# photoframe.net
KiCad netlist of a schematic drawn in EAGLE
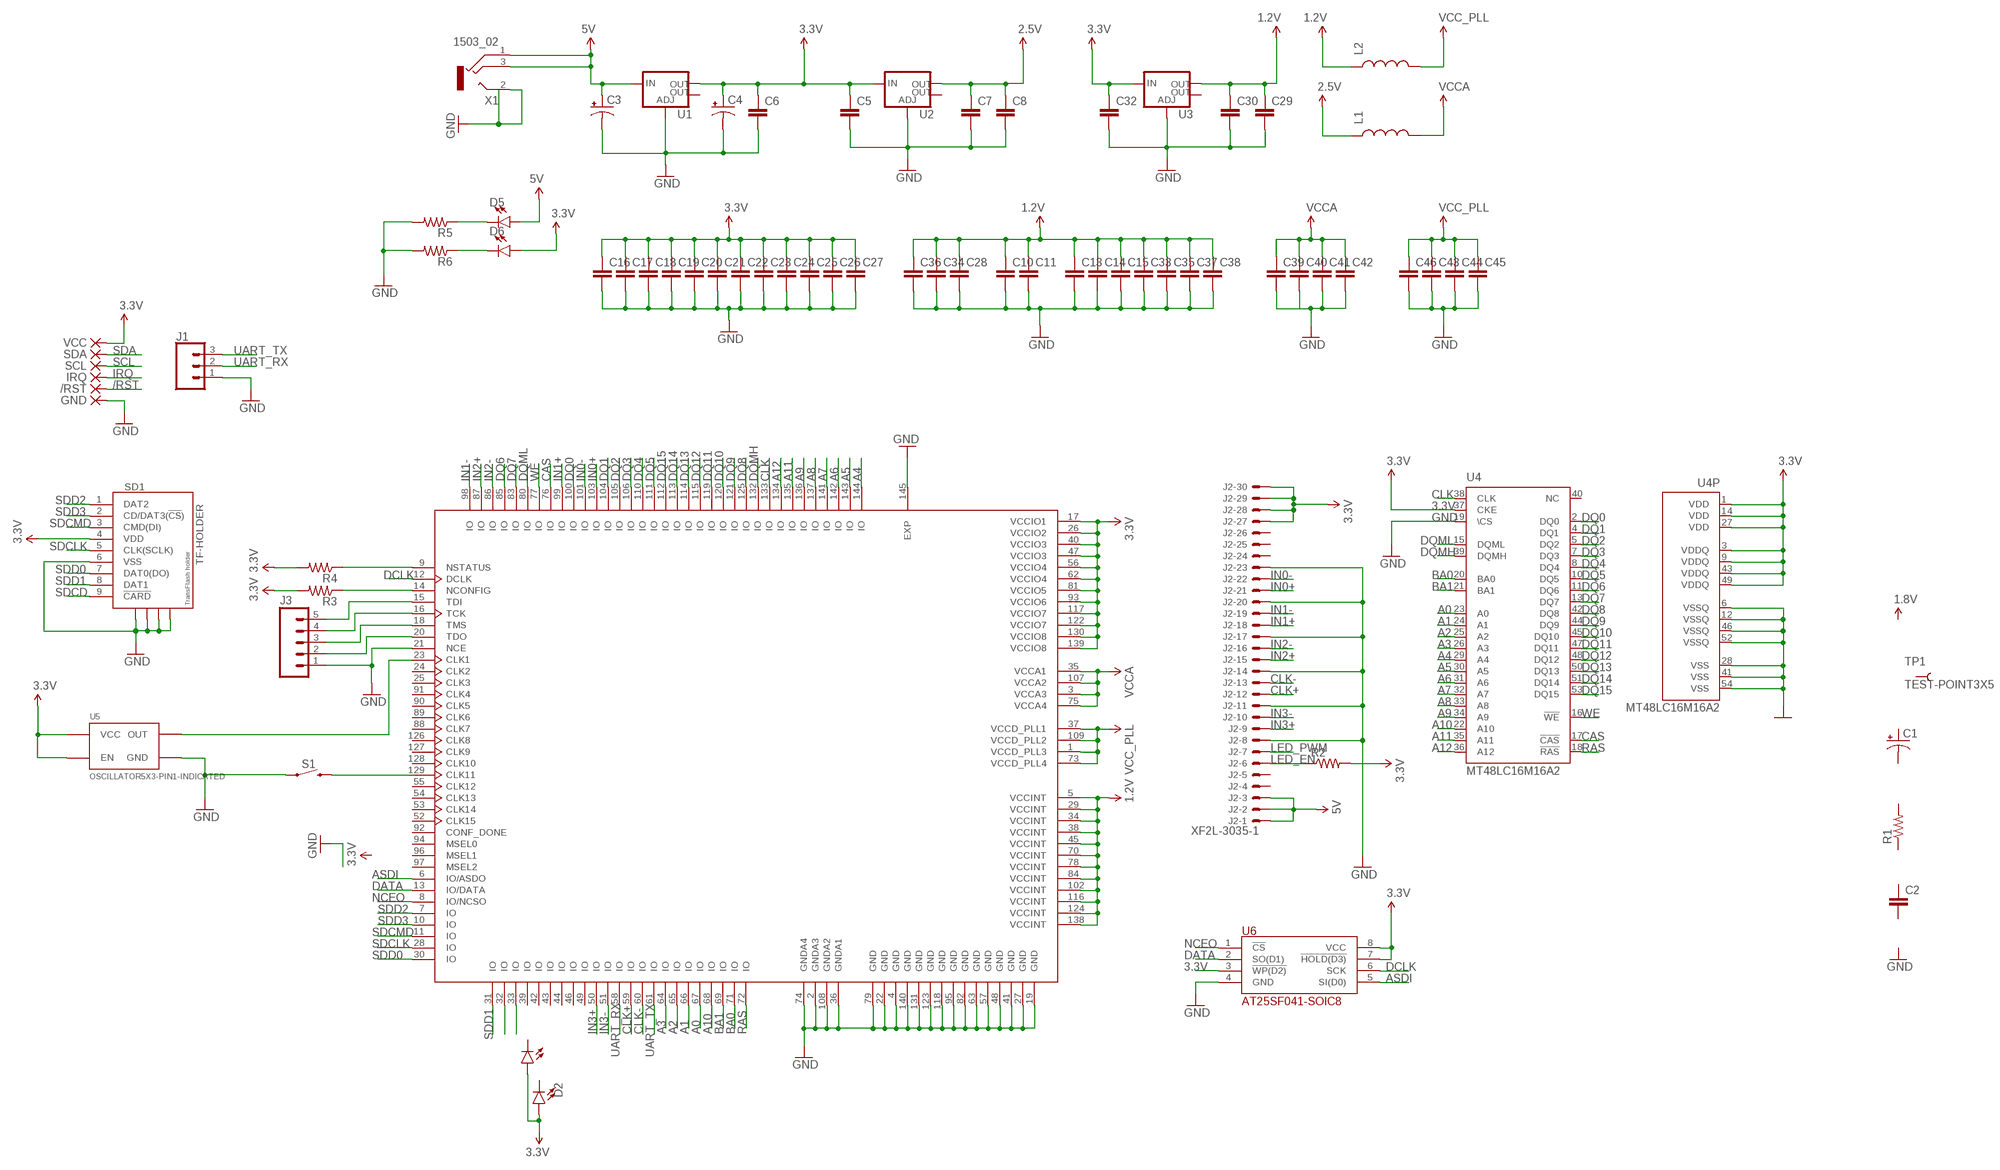
[diagram p0: schematic, sheet 1]

(export (version "E")
  (design (tool "Eeschema 10.0.6"))
  (components
    (comp (ref "/RST")
      (value "PAD-SMD15R")
      (footprint "eagle-import:SMD15R")
      (libsource (lib "eagle-import") (part "PAD-SMD15R"))
    )
    (comp (ref "C1")
      (value "CAP_POL1206-KIT")
      (footprint "eagle-import:EIA3216-KIT")
      (libsource (lib "eagle-import") (part "CAP_POL1206-KIT"))
    )
    (comp (ref "C2")
      (value "CAP0603-CAP")
      (footprint "eagle-import:0603-CAP")
      (libsource (lib "eagle-import") (part "CAP0603-CAP"))
    )
    (comp (ref "C3")
      (value "CAP_POL1206-KIT")
      (footprint "eagle-import:EIA3216-KIT")
      (libsource (lib "eagle-import") (part "CAP_POL1206-KIT"))
    )
    (comp (ref "C4")
      (value "CAP_POL1206-KIT")
      (footprint "eagle-import:EIA3216-KIT")
      (libsource (lib "eagle-import") (part "CAP_POL1206-KIT"))
    )
    (comp (ref "C5")
      (value "CAP1206")
      (footprint "eagle-import:1206")
      (libsource (lib "eagle-import") (part "CAP1206"))
    )
    (comp (ref "C6")
      (value "CAP0805")
      (footprint "eagle-import:0805")
      (libsource (lib "eagle-import") (part "CAP0805"))
    )
    (comp (ref "C7")
      (value "CAP1206")
      (footprint "eagle-import:1206")
      (libsource (lib "eagle-import") (part "CAP1206"))
    )
    (comp (ref "C8")
      (value "CAP0603-CAP")
      (footprint "eagle-import:0603-CAP")
      (libsource (lib "eagle-import") (part "CAP0603-CAP"))
    )
    (comp (ref "C10")
      (value "CAP0402-CAP")
      (footprint "eagle-import:0402-CAP")
      (libsource (lib "eagle-import") (part "CAP0402-CAP"))
    )
    (comp (ref "C11")
      (value "CAP0402-CAP")
      (footprint "eagle-import:0402-CAP")
      (libsource (lib "eagle-import") (part "CAP0402-CAP"))
    )
    (comp (ref "C13")
      (value "CAP0402-CAP")
      (footprint "eagle-import:0402-CAP")
      (libsource (lib "eagle-import") (part "CAP0402-CAP"))
    )
    (comp (ref "C14")
      (value "CAP0402-CAP")
      (footprint "eagle-import:0402-CAP")
      (libsource (lib "eagle-import") (part "CAP0402-CAP"))
    )
    (comp (ref "C15")
      (value "CAP0402-CAP")
      (footprint "eagle-import:0402-CAP")
      (libsource (lib "eagle-import") (part "CAP0402-CAP"))
    )
    (comp (ref "C16")
      (value "CAP0402-CAP")
      (footprint "eagle-import:0402-CAP")
      (libsource (lib "eagle-import") (part "CAP0402-CAP"))
    )
    (comp (ref "C17")
      (value "CAP0402-CAP")
      (footprint "eagle-import:0402-CAP")
      (libsource (lib "eagle-import") (part "CAP0402-CAP"))
    )
    (comp (ref "C18")
      (value "CAP0402-CAP")
      (footprint "eagle-import:0402-CAP")
      (libsource (lib "eagle-import") (part "CAP0402-CAP"))
    )
    (comp (ref "C19")
      (value "CAP0402-CAP")
      (footprint "eagle-import:0402-CAP")
      (libsource (lib "eagle-import") (part "CAP0402-CAP"))
    )
    (comp (ref "C20")
      (value "CAP0402-CAP")
      (footprint "eagle-import:0402-CAP")
      (libsource (lib "eagle-import") (part "CAP0402-CAP"))
    )
    (comp (ref "C21")
      (value "CAP0402-CAP")
      (footprint "eagle-import:0402-CAP")
      (libsource (lib "eagle-import") (part "CAP0402-CAP"))
    )
    (comp (ref "C22")
      (value "CAP0402-CAP")
      (footprint "eagle-import:0402-CAP")
      (libsource (lib "eagle-import") (part "CAP0402-CAP"))
    )
    (comp (ref "C23")
      (value "CAP0402-CAP")
      (footprint "eagle-import:0402-CAP")
      (libsource (lib "eagle-import") (part "CAP0402-CAP"))
    )
    (comp (ref "C24")
      (value "CAP0402-CAP")
      (footprint "eagle-import:0402-CAP")
      (libsource (lib "eagle-import") (part "CAP0402-CAP"))
    )
    (comp (ref "C25")
      (value "CAP0402-CAP")
      (footprint "eagle-import:0402-CAP")
      (libsource (lib "eagle-import") (part "CAP0402-CAP"))
    )
    (comp (ref "C26")
      (value "CAP0402-CAP")
      (footprint "eagle-import:0402-CAP")
      (libsource (lib "eagle-import") (part "CAP0402-CAP"))
    )
    (comp (ref "C27")
      (value "CAP0402-CAP")
      (footprint "eagle-import:0402-CAP")
      (libsource (lib "eagle-import") (part "CAP0402-CAP"))
    )
    (comp (ref "C28")
      (value "CAP0402-CAP")
      (footprint "eagle-import:0402-CAP")
      (libsource (lib "eagle-import") (part "CAP0402-CAP"))
    )
    (comp (ref "C29")
      (value "CAP0805")
      (footprint "eagle-import:0805")
      (libsource (lib "eagle-import") (part "CAP0805"))
    )
    (comp (ref "C30")
      (value "CAP1206")
      (footprint "eagle-import:1206")
      (libsource (lib "eagle-import") (part "CAP1206"))
    )
    (comp (ref "C32")
      (value "CAP1206")
      (footprint "eagle-import:1206")
      (libsource (lib "eagle-import") (part "CAP1206"))
    )
    (comp (ref "C33")
      (value "CAP0402-CAP")
      (footprint "eagle-import:0402-CAP")
      (libsource (lib "eagle-import") (part "CAP0402-CAP"))
    )
    (comp (ref "C34")
      (value "CAP0402-CAP")
      (footprint "eagle-import:0402-CAP")
      (libsource (lib "eagle-import") (part "CAP0402-CAP"))
    )
    (comp (ref "C35")
      (value "CAP0402-CAP")
      (footprint "eagle-import:0402-CAP")
      (libsource (lib "eagle-import") (part "CAP0402-CAP"))
    )
    (comp (ref "C36")
      (value "CAP0402-CAP")
      (footprint "eagle-import:0402-CAP")
      (libsource (lib "eagle-import") (part "CAP0402-CAP"))
    )
    (comp (ref "C37")
      (value "CAP0402-CAP")
      (footprint "eagle-import:0402-CAP")
      (libsource (lib "eagle-import") (part "CAP0402-CAP"))
    )
    (comp (ref "C38")
      (value "CAP0402-CAP")
      (footprint "eagle-import:0402-CAP")
      (libsource (lib "eagle-import") (part "CAP0402-CAP"))
    )
    (comp (ref "C39")
      (value "CAP0402-CAP")
      (footprint "eagle-import:0402-CAP")
      (libsource (lib "eagle-import") (part "CAP0402-CAP"))
    )
    (comp (ref "C40")
      (value "CAP0402-CAP")
      (footprint "eagle-import:0402-CAP")
      (libsource (lib "eagle-import") (part "CAP0402-CAP"))
    )
    (comp (ref "C41")
      (value "CAP0402-CAP")
      (footprint "eagle-import:0402-CAP")
      (libsource (lib "eagle-import") (part "CAP0402-CAP"))
    )
    (comp (ref "C42")
      (value "CAP0402-CAP")
      (footprint "eagle-import:0402-CAP")
      (libsource (lib "eagle-import") (part "CAP0402-CAP"))
    )
    (comp (ref "C43")
      (value "CAP0402-CAP")
      (footprint "eagle-import:0402-CAP")
      (libsource (lib "eagle-import") (part "CAP0402-CAP"))
    )
    (comp (ref "C44")
      (value "CAP0402-CAP")
      (footprint "eagle-import:0402-CAP")
      (libsource (lib "eagle-import") (part "CAP0402-CAP"))
    )
    (comp (ref "C45")
      (value "CAP0805")
      (footprint "eagle-import:0805")
      (libsource (lib "eagle-import") (part "CAP0805"))
    )
    (comp (ref "C46")
      (value "CAP0402-CAP")
      (footprint "eagle-import:0402-CAP")
      (libsource (lib "eagle-import") (part "CAP0402-CAP"))
    )
    (comp (ref "D1")
      (value "LED0603")
      (footprint "eagle-import:LED-0603")
      (libsource (lib "eagle-import") (part "LED0603"))
    )
    (comp (ref "D2")
      (value "LED0603")
      (footprint "eagle-import:LED-0603")
      (libsource (lib "eagle-import") (part "LED0603"))
    )
    (comp (ref "D5")
      (value "LED1206")
      (footprint "eagle-import:LED-1206")
      (libsource (lib "eagle-import") (part "LED1206"))
    )
    (comp (ref "D6")
      (value "LED1206")
      (footprint "eagle-import:LED-1206")
      (libsource (lib "eagle-import") (part "LED1206"))
    )
    (comp (ref "GND")
      (value "PAD-SMD14R")
      (footprint "eagle-import:SMD14R")
      (libsource (lib "eagle-import") (part "PAD-SMD14R"))
    )
    (comp (ref "IRQ")
      (value "PAD-SMD15R")
      (footprint "eagle-import:SMD15R")
      (libsource (lib "eagle-import") (part "PAD-SMD15R"))
    )
    (comp (ref "J1")
      (value "CONN_03LONGPADS")
      (footprint "eagle-import:1X03_LONGPADS")
      (libsource (lib "eagle-import") (part "CONN_03LONGPADS"))
    )
    (comp (ref "J2")
      (value "XF2L-3035-1")
      (footprint "eagle-import:XF2L-3035-1")
      (fields (field (name "MPN") "XF2L-3035-1A"))
      (libsource (lib "eagle-import") (part "XF2-30?35-1L"))
    )
    (comp (ref "J3")
      (value "M05PTH_LONGPADS")
      (footprint "eagle-import:1X05_LONGPADS")
      (libsource (lib "eagle-import") (part "M05PTH_LONGPADS"))
    )
    (comp (ref "L1")
      (value "INDUCTOR0805-IND")
      (footprint "eagle-import:0805")
      (libsource (lib "eagle-import") (part "INDUCTOR0805-IND"))
    )
    (comp (ref "L2")
      (value "INDUCTOR0805-IND")
      (footprint "eagle-import:0805")
      (libsource (lib "eagle-import") (part "INDUCTOR0805-IND"))
    )
    (comp (ref "R1")
      (value "RESISTOR0603-RES")
      (footprint "eagle-import:0603-RES")
      (libsource (lib "eagle-import") (part "RESISTOR0603-RES"))
    )
    (comp (ref "R2")
      (value "RESISTOR0402-RES")
      (footprint "eagle-import:0402-RES")
      (libsource (lib "eagle-import") (part "RESISTOR0402-RES"))
    )
    (comp (ref "R3")
      (value "RESISTOR0402-RES")
      (footprint "eagle-import:0402-RES")
      (libsource (lib "eagle-import") (part "RESISTOR0402-RES"))
    )
    (comp (ref "R4")
      (value "RESISTOR0402-RES")
      (footprint "eagle-import:0402-RES")
      (libsource (lib "eagle-import") (part "RESISTOR0402-RES"))
    )
    (comp (ref "R5")
      (value "RESISTOR0603-RES")
      (footprint "eagle-import:0603-RES")
      (libsource (lib "eagle-import") (part "RESISTOR0603-RES"))
    )
    (comp (ref "R6")
      (value "RESISTOR0603-RES")
      (footprint "eagle-import:0603-RES")
      (libsource (lib "eagle-import") (part "RESISTOR0603-RES"))
    )
    (comp (ref "S1")
      (value "MOMENTARY-SWITCH-SPST-SMD-5.2-TALL-REDUNDANT")
      (footprint "eagle-import:TACTILE_SWITCH_SMD_5.2MM")
      (libsource (lib "eagle-import") (part "MOMENTARY-SWITCH-SPST-SMD-5.2-TALL-REDUNDANT"))
    )
    (comp (ref "SCL")
      (value "PAD-SMD15R")
      (footprint "eagle-import:SMD15R")
      (libsource (lib "eagle-import") (part "PAD-SMD15R"))
    )
    (comp (ref "SD1")
      (value "TF-HOLDER")
      (footprint "eagle-import:TF-PULL")
      (libsource (lib "eagle-import") (part "TF-HOLDER"))
    )
    (comp (ref "SDA")
      (value "PAD-SMD15R")
      (footprint "eagle-import:SMD15R")
      (libsource (lib "eagle-import") (part "PAD-SMD15R"))
    )
    (comp (ref "TP1")
      (value "TEST-POINT3X5")
      (footprint "eagle-import:PAD.03X.05")
      (libsource (lib "eagle-import") (part "TEST-POINT3X5"))
    )
    (comp (ref "U0")
      (value "EP4CE15E22")
      (footprint "eagle-import:QFP50P2200X2200X165-145N")
      (libsource (lib "eagle-import") (part "EP4CE15E22"))
    )
    (comp (ref "U1")
      (value "V_REG_LM1117SOT223")
      (footprint "eagle-import:SOT223")
      (libsource (lib "eagle-import") (part "V_REG_LM1117SOT223"))
    )
    (comp (ref "U2")
      (value "V_REG_LM1117SOT223")
      (footprint "eagle-import:SOT223")
      (libsource (lib "eagle-import") (part "V_REG_LM1117SOT223"))
    )
    (comp (ref "U3")
      (value "V_REG_LM1117SOT223")
      (footprint "eagle-import:SOT223")
      (libsource (lib "eagle-import") (part "V_REG_LM1117SOT223"))
    )
    (comp (ref "U4")
      (value "MT48LC16M16A2")
      (footprint "eagle-import:TSOP54-400")
      (libsource (lib "eagle-import") (part "MT48LC16M16A2"))
    )
    (comp (ref "U5")
      (value "OSCILLATOR5X3-PIN1-INDICATED")
      (footprint "eagle-import:CRYSTAL-OSC-SMD-5X3")
      (libsource (lib "eagle-import") (part "OSCILLATOR5X3-PIN1-INDICATED"))
    )
    (comp (ref "U6")
      (value "AT25SF041-SOIC8")
      (footprint "eagle-import:SO08")
      (libsource (lib "eagle-import") (part "AT25SF041"))
    )
    (comp (ref "VCC")
      (value "PAD-SMD15R")
      (footprint "eagle-import:SMD15R")
      (libsource (lib "eagle-import") (part "PAD-SMD15R"))
    )
    (comp (ref "X1")
      (value "1503_02")
      (footprint "eagle-import:1503_02")
      (libsource (lib "eagle-import") (part "1503_02"))
    )
  )
  (nets
    (net (code "1") (name "/A0") (class "Default")
      (node (ref "U0") (pin "67") (pinfunction "IO_67") (pintype "bidirectional"))
      (node (ref "U4") (pin "23") (pinfunction "A0_23") (pintype "input"))
    )
    (net (code "2") (name "/A1") (class "Default")
      (node (ref "U0") (pin "66") (pinfunction "IO_66") (pintype "bidirectional"))
      (node (ref "U4") (pin "24") (pinfunction "A1_24") (pintype "input"))
    )
    (net (code "3") (name "/A2") (class "Default")
      (node (ref "U0") (pin "65") (pinfunction "IO_65") (pintype "bidirectional"))
      (node (ref "U4") (pin "25") (pinfunction "A2_25") (pintype "input"))
    )
    (net (code "4") (name "/A3") (class "Default")
      (node (ref "U0") (pin "64") (pinfunction "IO_64") (pintype "bidirectional"))
      (node (ref "U4") (pin "26") (pinfunction "A3_26") (pintype "input"))
    )
    (net (code "5") (name "/A4") (class "Default")
      (node (ref "U0") (pin "144") (pinfunction "IO_144") (pintype "bidirectional"))
      (node (ref "U4") (pin "29") (pinfunction "A4_29") (pintype "input"))
    )
    (net (code "6") (name "/A5") (class "Default")
      (node (ref "U0") (pin "143") (pinfunction "IO_143") (pintype "bidirectional"))
      (node (ref "U4") (pin "30") (pinfunction "A5_30") (pintype "input"))
    )
    (net (code "7") (name "/A6") (class "Default")
      (node (ref "U0") (pin "142") (pinfunction "IO_142") (pintype "bidirectional"))
      (node (ref "U4") (pin "31") (pinfunction "A6_31") (pintype "input"))
    )
    (net (code "8") (name "/A7") (class "Default")
      (node (ref "U0") (pin "141") (pinfunction "IO_141") (pintype "bidirectional"))
      (node (ref "U4") (pin "32") (pinfunction "A7_32") (pintype "input"))
    )
    (net (code "9") (name "/A8") (class "Default")
      (node (ref "U0") (pin "137") (pinfunction "IO_137") (pintype "bidirectional"))
      (node (ref "U4") (pin "33") (pinfunction "A8_33") (pintype "input"))
    )
    (net (code "10") (name "/A9") (class "Default")
      (node (ref "U0") (pin "136") (pinfunction "IO_136") (pintype "bidirectional"))
      (node (ref "U4") (pin "34") (pinfunction "A9_34") (pintype "input"))
    )
    (net (code "11") (name "/A10") (class "Default")
      (node (ref "U0") (pin "68") (pinfunction "IO_68") (pintype "bidirectional"))
      (node (ref "U4") (pin "22") (pinfunction "A10_22") (pintype "input"))
    )
    (net (code "12") (name "/A11") (class "Default")
      (node (ref "U0") (pin "135") (pinfunction "IO_135") (pintype "bidirectional"))
      (node (ref "U4") (pin "35") (pinfunction "A11_35") (pintype "input"))
    )
    (net (code "13") (name "/A12") (class "Default")
      (node (ref "U0") (pin "134") (pinfunction "IO_134") (pintype "bidirectional"))
      (node (ref "U4") (pin "36") (pinfunction "A12_36") (pintype "input"))
    )
    (net (code "14") (name "/ASDI") (class "Default")
      (node (ref "U0") (pin "6") (pinfunction "IO/ASDO_6") (pintype "bidirectional"))
      (node (ref "U6") (pin "5") (pinfunction "SI(D0)_5") (pintype "bidirectional"))
    )
    (net (code "15") (name "/BA0") (class "Default")
      (node (ref "U0") (pin "71") (pinfunction "IO_71") (pintype "bidirectional"))
      (node (ref "U4") (pin "20") (pinfunction "BA0_20") (pintype "input"))
    )
    (net (code "16") (name "/BA1") (class "Default")
      (node (ref "U0") (pin "69") (pinfunction "IO_69") (pintype "bidirectional"))
      (node (ref "U4") (pin "21") (pinfunction "BA1_21") (pintype "input"))
    )
    (net (code "17") (name "/CAS") (class "Default")
      (node (ref "U0") (pin "76") (pinfunction "IO_76") (pintype "bidirectional"))
      (node (ref "U4") (pin "17") (pinfunction "~{CAS}_17") (pintype "input"))
    )
    (net (code "18") (name "/CLK") (class "Default")
      (node (ref "U0") (pin "133") (pinfunction "IO_133") (pintype "bidirectional"))
      (node (ref "U4") (pin "38") (pinfunction "CLK_38") (pintype "input"))
    )
    (net (code "19") (name "/CLK+") (class "Default")
      (node (ref "J2") (pin "12") (pinfunction "MS_12") (pintype "passive"))
      (node (ref "U0") (pin "59") (pinfunction "IO_59") (pintype "bidirectional"))
    )
    (net (code "20") (name "/CLK-") (class "Default")
      (node (ref "J2") (pin "13") (pinfunction "MS_13") (pintype "passive"))
      (node (ref "U0") (pin "60") (pinfunction "IO_60") (pintype "bidirectional"))
    )
    (net (code "21") (name "/DATA") (class "Default")
      (node (ref "U0") (pin "13") (pinfunction "IO/DATA_13") (pintype "bidirectional"))
      (node (ref "U6") (pin "2") (pinfunction "SO(D1)_2") (pintype "bidirectional"))
    )
    (net (code "22") (name "/DCLK") (class "Default")
      (node (ref "U0") (pin "12") (pinfunction "DCLK_12") (pintype "bidirectional"))
      (node (ref "U6") (pin "6") (pinfunction "SCK_6") (pintype "bidirectional"))
    )
    (net (code "23") (name "/DQ0") (class "Default")
      (node (ref "U0") (pin "100") (pinfunction "IO_100") (pintype "bidirectional"))
      (node (ref "U4") (pin "2") (pinfunction "DQ0_2") (pintype "tri_state"))
    )
    (net (code "24") (name "/DQ1") (class "Default")
      (node (ref "U0") (pin "104") (pinfunction "IO_104") (pintype "bidirectional"))
      (node (ref "U4") (pin "4") (pinfunction "DQ1_4") (pintype "tri_state"))
    )
    (net (code "25") (name "/DQ2") (class "Default")
      (node (ref "U0") (pin "105") (pinfunction "IO_105") (pintype "bidirectional"))
      (node (ref "U4") (pin "5") (pinfunction "DQ2_5") (pintype "tri_state"))
    )
    (net (code "26") (name "/DQ3") (class "Default")
      (node (ref "U0") (pin "106") (pinfunction "IO_106") (pintype "bidirectional"))
      (node (ref "U4") (pin "7") (pinfunction "DQ3_7") (pintype "tri_state"))
    )
    (net (code "27") (name "/DQ4") (class "Default")
      (node (ref "U0") (pin "110") (pinfunction "IO_110") (pintype "bidirectional"))
      (node (ref "U4") (pin "8") (pinfunction "DQ4_8") (pintype "tri_state"))
    )
    (net (code "28") (name "/DQ5") (class "Default")
      (node (ref "U0") (pin "111") (pinfunction "IO_111") (pintype "bidirectional"))
      (node (ref "U4") (pin "10") (pinfunction "DQ5_10") (pintype "tri_state"))
    )
    (net (code "29") (name "/DQ6") (class "Default")
      (node (ref "U0") (pin "85") (pinfunction "IO_85") (pintype "bidirectional"))
      (node (ref "U4") (pin "11") (pinfunction "DQ6_11") (pintype "tri_state"))
    )
    (net (code "30") (name "/DQ7") (class "Default")
      (node (ref "U0") (pin "83") (pinfunction "IO_83") (pintype "bidirectional"))
      (node (ref "U4") (pin "13") (pinfunction "DQ7_13") (pintype "tri_state"))
    )
    (net (code "31") (name "/DQ8") (class "Default")
      (node (ref "U0") (pin "125") (pinfunction "IO_125") (pintype "bidirectional"))
      (node (ref "U4") (pin "42") (pinfunction "DQ8_42") (pintype "tri_state"))
    )
    (net (code "32") (name "/DQ9") (class "Default")
      (node (ref "U0") (pin "121") (pinfunction "IO_121") (pintype "bidirectional"))
      (node (ref "U4") (pin "44") (pinfunction "DQ9_44") (pintype "tri_state"))
    )
    (net (code "33") (name "/DQ10") (class "Default")
      (node (ref "U0") (pin "120") (pinfunction "IO_120") (pintype "bidirectional"))
      (node (ref "U4") (pin "45") (pinfunction "DQ10_45") (pintype "tri_state"))
    )
    (net (code "34") (name "/DQ11") (class "Default")
      (node (ref "U0") (pin "119") (pinfunction "IO_119") (pintype "bidirectional"))
      (node (ref "U4") (pin "47") (pinfunction "DQ11_47") (pintype "tri_state"))
    )
    (net (code "35") (name "/DQ12") (class "Default")
      (node (ref "U0") (pin "115") (pinfunction "IO_115") (pintype "bidirectional"))
      (node (ref "U4") (pin "48") (pinfunction "DQ12_48") (pintype "tri_state"))
    )
    (net (code "36") (name "/DQ13") (class "Default")
      (node (ref "U0") (pin "114") (pinfunction "IO_114") (pintype "bidirectional"))
      (node (ref "U4") (pin "50") (pinfunction "DQ13_50") (pintype "tri_state"))
    )
    (net (code "37") (name "/DQ14") (class "Default")
      (node (ref "U0") (pin "113") (pinfunction "IO_113") (pintype "bidirectional"))
      (node (ref "U4") (pin "51") (pinfunction "DQ14_51") (pintype "tri_state"))
    )
    (net (code "38") (name "/DQ15") (class "Default")
      (node (ref "U0") (pin "112") (pinfunction "IO_112") (pintype "bidirectional"))
      (node (ref "U4") (pin "53") (pinfunction "DQ15_53") (pintype "tri_state"))
    )
    (net (code "39") (name "/DQMH") (class "Default")
      (node (ref "U0") (pin "132") (pinfunction "IO_132") (pintype "bidirectional"))
      (node (ref "U4") (pin "39") (pinfunction "DQMH_39") (pintype "input"))
    )
    (net (code "40") (name "/DQML") (class "Default")
      (node (ref "U0") (pin "80") (pinfunction "IO_80") (pintype "bidirectional"))
      (node (ref "U4") (pin "15") (pinfunction "DQML_15") (pintype "input"))
    )
    (net (code "41") (name "/IN0+") (class "Default")
      (node (ref "J2") (pin "21") (pinfunction "MS_21") (pintype "passive"))
      (node (ref "U0") (pin "103") (pinfunction "IO_103") (pintype "bidirectional"))
    )
    (net (code "42") (name "/IN0-") (class "Default")
      (node (ref "J2") (pin "22") (pinfunction "MS_22") (pintype "passive"))
      (node (ref "U0") (pin "101") (pinfunction "IO_101") (pintype "bidirectional"))
    )
    (net (code "43") (name "/IN1+") (class "Default")
      (node (ref "J2") (pin "18") (pinfunction "MS_18") (pintype "passive"))
      (node (ref "U0") (pin "99") (pinfunction "IO_99") (pintype "bidirectional"))
    )
    (net (code "44") (name "/IN1-") (class "Default")
      (node (ref "J2") (pin "19") (pinfunction "MS_19") (pintype "passive"))
      (node (ref "U0") (pin "98") (pinfunction "IO_98") (pintype "bidirectional"))
    )
    (net (code "45") (name "/IN2+") (class "Default")
      (node (ref "J2") (pin "15") (pinfunction "MS_15") (pintype "passive"))
      (node (ref "U0") (pin "87") (pinfunction "IO_87") (pintype "bidirectional"))
    )
    (net (code "46") (name "/IN2-") (class "Default")
      (node (ref "J2") (pin "16") (pinfunction "MS_16") (pintype "passive"))
      (node (ref "U0") (pin "86") (pinfunction "IO_86") (pintype "bidirectional"))
    )
    (net (code "47") (name "/IN3+") (class "Default")
      (node (ref "J2") (pin "9") (pinfunction "MS_9") (pintype "passive"))
      (node (ref "U0") (pin "50") (pinfunction "IO_50") (pintype "bidirectional"))
    )
    (net (code "48") (name "/IN3-") (class "Default")
      (node (ref "J2") (pin "10") (pinfunction "MS_10") (pintype "passive"))
      (node (ref "U0") (pin "51") (pinfunction "IO_51") (pintype "bidirectional"))
    )
    (net (code "49") (name "/IRQ") (class "Default")
      (node (ref "IRQ") (pin "PAD") (pinfunction "P_PAD") (pintype "passive"))
    )
    (net (code "50") (name "/LED_EN") (class "Default")
      (node (ref "J2") (pin "6") (pinfunction "MS_6") (pintype "passive"))
      (node (ref "R2") (pin "1") (pinfunction "1_1") (pintype "passive"))
    )
    (net (code "51") (name "/LED_PWM") (class "Default")
      (node (ref "J2") (pin "7") (pinfunction "MS_7") (pintype "passive"))
    )
    (net (code "52") (name "/NCEO") (class "Default")
      (node (ref "U0") (pin "8") (pinfunction "IO/NCSO_8") (pintype "bidirectional"))
      (node (ref "U6") (pin "1") (pinfunction "~{CS}_1") (pintype "bidirectional"))
    )
    (net (code "53") (name "/RAS") (class "Default")
      (node (ref "U0") (pin "72") (pinfunction "IO_72") (pintype "bidirectional"))
      (node (ref "U4") (pin "18") (pinfunction "~{RAS}_18") (pintype "input"))
    )
    (net (code "54") (name "/SCL") (class "Default")
      (node (ref "SCL") (pin "PAD") (pinfunction "P_PAD") (pintype "passive"))
    )
    (net (code "55") (name "/SDA") (class "Default")
      (node (ref "SDA") (pin "PAD") (pinfunction "P_PAD") (pintype "passive"))
    )
    (net (code "56") (name "/SDCD") (class "Default")
      (node (ref "SD1") (pin "9") (pinfunction "~{CARD}_9") (pintype "passive"))
    )
    (net (code "57") (name "/SDCLK") (class "Default")
      (node (ref "SD1") (pin "5") (pinfunction "CLK(SCLK)_5") (pintype "input"))
      (node (ref "U0") (pin "28") (pinfunction "IO_28") (pintype "bidirectional"))
    )
    (net (code "58") (name "/SDCMD") (class "Default")
      (node (ref "SD1") (pin "3") (pinfunction "CMD(DI)_3") (pintype "bidirectional"))
      (node (ref "U0") (pin "11") (pinfunction "IO_11") (pintype "bidirectional"))
    )
    (net (code "59") (name "/SDD0") (class "Default")
      (node (ref "SD1") (pin "7") (pinfunction "DAT0(DO)_7") (pintype "bidirectional"))
      (node (ref "U0") (pin "30") (pinfunction "IO_30") (pintype "bidirectional"))
    )
    (net (code "60") (name "/SDD1") (class "Default")
      (node (ref "SD1") (pin "8") (pinfunction "DAT1_8") (pintype "bidirectional"))
      (node (ref "U0") (pin "31") (pinfunction "IO_31") (pintype "bidirectional"))
    )
    (net (code "61") (name "/SDD2") (class "Default")
      (node (ref "SD1") (pin "1") (pinfunction "DAT2_1") (pintype "bidirectional"))
      (node (ref "U0") (pin "7") (pinfunction "IO_7") (pintype "bidirectional"))
    )
    (net (code "62") (name "/SDD3") (class "Default")
      (node (ref "SD1") (pin "2") (pinfunction "CD/DAT3(~{CS})_2") (pintype "bidirectional"))
      (node (ref "U0") (pin "10") (pinfunction "IO_10") (pintype "bidirectional"))
    )
    (net (code "63") (name "/UART_RX") (class "Default")
      (node (ref "J1") (pin "2") (pinfunction "2_2") (pintype "passive"))
      (node (ref "U0") (pin "58") (pinfunction "IO_58") (pintype "bidirectional"))
    )
    (net (code "64") (name "/UART_TX") (class "Default")
      (node (ref "J1") (pin "3") (pinfunction "3_3") (pintype "passive"))
      (node (ref "U0") (pin "61") (pinfunction "IO_61") (pintype "bidirectional"))
    )
    (net (code "65") (name "/WE") (class "Default")
      (node (ref "U0") (pin "77") (pinfunction "IO_77") (pintype "bidirectional"))
      (node (ref "U4") (pin "16") (pinfunction "~{WE}_16") (pintype "input"))
    )
    (net (code "66") (name "/{slash}RST") (class "Default")
      (node (ref "/RST") (pin "PAD") (pinfunction "P_PAD") (pintype "passive"))
    )
    (net (code "67") (name "1.2V") (class "Default")
      (node (ref "C10") (pin "1") (pinfunction "1_1") (pintype "passive"))
      (node (ref "C11") (pin "1") (pinfunction "1_1") (pintype "passive"))
      (node (ref "C13") (pin "1") (pinfunction "1_1") (pintype "passive"))
      (node (ref "C14") (pin "1") (pinfunction "1_1") (pintype "passive"))
      (node (ref "C15") (pin "1") (pinfunction "1_1") (pintype "passive"))
      (node (ref "C28") (pin "1") (pinfunction "1_1") (pintype "passive"))
      (node (ref "C29") (pin "1") (pinfunction "1_1") (pintype "passive"))
      (node (ref "C30") (pin "1") (pinfunction "1_1") (pintype "passive"))
      (node (ref "C33") (pin "1") (pinfunction "1_1") (pintype "passive"))
      (node (ref "C34") (pin "1") (pinfunction "1_1") (pintype "passive"))
      (node (ref "C35") (pin "1") (pinfunction "1_1") (pintype "passive"))
      (node (ref "C36") (pin "1") (pinfunction "1_1") (pintype "passive"))
      (node (ref "C37") (pin "1") (pinfunction "1_1") (pintype "passive"))
      (node (ref "C38") (pin "1") (pinfunction "1_1") (pintype "passive"))
      (node (ref "L2") (pin "1") (pinfunction "1_1") (pintype "passive"))
      (node (ref "U0") (pin "102") (pinfunction "VCCINT_102") (pintype "power_in"))
      (node (ref "U0") (pin "116") (pinfunction "VCCINT_116") (pintype "power_in"))
      (node (ref "U0") (pin "124") (pinfunction "VCCINT_124") (pintype "power_in"))
      (node (ref "U0") (pin "138") (pinfunction "VCCINT_138") (pintype "power_in"))
      (node (ref "U0") (pin "29") (pinfunction "VCCINT_29") (pintype "power_in"))
      (node (ref "U0") (pin "34") (pinfunction "VCCINT_34") (pintype "power_in"))
      (node (ref "U0") (pin "38") (pinfunction "VCCINT_38") (pintype "power_in"))
      (node (ref "U0") (pin "45") (pinfunction "VCCINT_45") (pintype "power_in"))
      (node (ref "U0") (pin "5") (pinfunction "VCCINT_5") (pintype "power_in"))
      (node (ref "U0") (pin "70") (pinfunction "VCCINT_70") (pintype "power_in"))
      (node (ref "U0") (pin "78") (pinfunction "VCCINT_78") (pintype "power_in"))
      (node (ref "U0") (pin "84") (pinfunction "VCCINT_84") (pintype "power_in"))
      (node (ref "U3") (pin "2") (pinfunction "OUT_2") (pintype "output"))
    )
    (net (code "69") (name "2.5V") (class "Default")
      (node (ref "C7") (pin "1") (pinfunction "1_1") (pintype "passive"))
      (node (ref "C8") (pin "1") (pinfunction "1_1") (pintype "passive"))
      (node (ref "L1") (pin "1") (pinfunction "1_1") (pintype "passive"))
      (node (ref "U2") (pin "2") (pinfunction "OUT_2") (pintype "output"))
    )
    (net (code "70") (name "3.3V") (class "Default")
      (node (ref "C16") (pin "1") (pinfunction "1_1") (pintype "passive"))
      (node (ref "C17") (pin "1") (pinfunction "1_1") (pintype "passive"))
      (node (ref "C18") (pin "1") (pinfunction "1_1") (pintype "passive"))
      (node (ref "C19") (pin "1") (pinfunction "1_1") (pintype "passive"))
      (node (ref "C20") (pin "1") (pinfunction "1_1") (pintype "passive"))
      (node (ref "C21") (pin "1") (pinfunction "1_1") (pintype "passive"))
      (node (ref "C22") (pin "1") (pinfunction "1_1") (pintype "passive"))
      (node (ref "C23") (pin "1") (pinfunction "1_1") (pintype "passive"))
      (node (ref "C24") (pin "1") (pinfunction "1_1") (pintype "passive"))
      (node (ref "C25") (pin "1") (pinfunction "1_1") (pintype "passive"))
      (node (ref "C26") (pin "1") (pinfunction "1_1") (pintype "passive"))
      (node (ref "C27") (pin "1") (pinfunction "1_1") (pintype "passive"))
      (node (ref "C32") (pin "1") (pinfunction "1_1") (pintype "passive"))
      (node (ref "C4") (pin "A") (pinfunction "+_A") (pintype "passive"))
      (node (ref "C5") (pin "1") (pinfunction "1_1") (pintype "passive"))
      (node (ref "C6") (pin "1") (pinfunction "1_1") (pintype "passive"))
      (node (ref "D1") (pin "A") (pinfunction "A_A") (pintype "passive"))
      (node (ref "D2") (pin "A") (pinfunction "A_A") (pintype "passive"))
      (node (ref "D6") (pin "A") (pinfunction "A_A") (pintype "passive"))
      (node (ref "J2") (pin "27") (pinfunction "MS_27") (pintype "passive"))
      (node (ref "J2") (pin "28") (pinfunction "MS_28") (pintype "passive"))
      (node (ref "J2") (pin "29") (pinfunction "MS_29") (pintype "passive"))
      (node (ref "J2") (pin "30") (pinfunction "MS_30") (pintype "passive"))
      (node (ref "R2") (pin "2") (pinfunction "2_2") (pintype "passive"))
      (node (ref "R3") (pin "2") (pinfunction "2_2") (pintype "passive"))
      (node (ref "R4") (pin "2") (pinfunction "2_2") (pintype "passive"))
      (node (ref "SD1") (pin "4") (pinfunction "VDD_4") (pintype "power_in"))
      (node (ref "U0") (pin "117") (pinfunction "VCCIO7_117") (pintype "power_in"))
      (node (ref "U0") (pin "122") (pinfunction "VCCIO7_122") (pintype "power_in"))
      (node (ref "U0") (pin "130") (pinfunction "VCCIO8_130") (pintype "power_in"))
      (node (ref "U0") (pin "139") (pinfunction "VCCIO8_139") (pintype "power_in"))
      (node (ref "U0") (pin "17") (pinfunction "VCCIO1_17") (pintype "power_in"))
      (node (ref "U0") (pin "26") (pinfunction "VCCIO2_26") (pintype "power_in"))
      (node (ref "U0") (pin "40") (pinfunction "VCCIO3_40") (pintype "power_in"))
      (node (ref "U0") (pin "47") (pinfunction "VCCIO3_47") (pintype "power_in"))
      (node (ref "U0") (pin "56") (pinfunction "VCCIO4_56") (pintype "power_in"))
      (node (ref "U0") (pin "62") (pinfunction "VCCIO4_62") (pintype "power_in"))
      (node (ref "U0") (pin "81") (pinfunction "VCCIO5_81") (pintype "power_in"))
      (node (ref "U0") (pin "93") (pinfunction "VCCIO6_93") (pintype "power_in"))
      (node (ref "U1") (pin "2") (pinfunction "OUT_2") (pintype "output"))
      (node (ref "U2") (pin "3") (pinfunction "IN_3") (pintype "input"))
      (node (ref "U3") (pin "3") (pinfunction "IN_3") (pintype "input"))
      (node (ref "U4") (pin "1") (pinfunction "VDD_1") (pintype "power_in"))
      (node (ref "U4") (pin "14") (pinfunction "VDD_14") (pintype "power_in"))
      (node (ref "U4") (pin "27") (pinfunction "VDD_27") (pintype "power_in"))
      (node (ref "U4") (pin "3") (pinfunction "VDDQ_3") (pintype "power_in"))
      (node (ref "U4") (pin "37") (pinfunction "CKE_37") (pintype "input"))
      (node (ref "U4") (pin "43") (pinfunction "VDDQ_43") (pintype "power_in"))
      (node (ref "U4") (pin "49") (pinfunction "VDDQ_49") (pintype "power_in"))
      (node (ref "U4") (pin "9") (pinfunction "VDDQ_9") (pintype "power_in"))
      (node (ref "U5") (pin "1") (pinfunction "EN_1") (pintype "bidirectional"))
      (node (ref "U5") (pin "4") (pinfunction "VCC_4") (pintype "bidirectional"))
      (node (ref "U6") (pin "3") (pinfunction "~{WP(D2})_3") (pintype "bidirectional"))
      (node (ref "U6") (pin "7") (pinfunction "~{HOLD(D3})_7") (pintype "bidirectional"))
      (node (ref "U6") (pin "8") (pinfunction "VCC_8") (pintype "bidirectional"))
      (node (ref "VCC") (pin "PAD") (pinfunction "P_PAD") (pintype "passive"))
    )
    (net (code "71") (name "5V") (class "Default")
      (node (ref "C3") (pin "A") (pinfunction "+_A") (pintype "passive"))
      (node (ref "D5") (pin "A") (pinfunction "A_A") (pintype "passive"))
      (node (ref "J2") (pin "1") (pinfunction "MSV_1") (pintype "passive"))
      (node (ref "J2") (pin "2") (pinfunction "MS_2") (pintype "passive"))
      (node (ref "J2") (pin "3") (pinfunction "MS_3") (pintype "passive"))
      (node (ref "U1") (pin "3") (pinfunction "IN_3") (pintype "input"))
      (node (ref "X1") (pin "1") (pinfunction "1_1") (pintype "passive"))
      (node (ref "X1") (pin "3") (pinfunction "3_3") (pintype "passive"))
    )
    (net (code "72") (name "GND") (class "Default")
      (node (ref "C10") (pin "2") (pinfunction "2_2") (pintype "passive"))
      (node (ref "C11") (pin "2") (pinfunction "2_2") (pintype "passive"))
      (node (ref "C13") (pin "2") (pinfunction "2_2") (pintype "passive"))
      (node (ref "C14") (pin "2") (pinfunction "2_2") (pintype "passive"))
      (node (ref "C15") (pin "2") (pinfunction "2_2") (pintype "passive"))
      (node (ref "C16") (pin "2") (pinfunction "2_2") (pintype "passive"))
      (node (ref "C17") (pin "2") (pinfunction "2_2") (pintype "passive"))
      (node (ref "C18") (pin "2") (pinfunction "2_2") (pintype "passive"))
      (node (ref "C19") (pin "2") (pinfunction "2_2") (pintype "passive"))
      (node (ref "C20") (pin "2") (pinfunction "2_2") (pintype "passive"))
      (node (ref "C21") (pin "2") (pinfunction "2_2") (pintype "passive"))
      (node (ref "C22") (pin "2") (pinfunction "2_2") (pintype "passive"))
      (node (ref "C23") (pin "2") (pinfunction "2_2") (pintype "passive"))
      (node (ref "C24") (pin "2") (pinfunction "2_2") (pintype "passive"))
      (node (ref "C25") (pin "2") (pinfunction "2_2") (pintype "passive"))
      (node (ref "C26") (pin "2") (pinfunction "2_2") (pintype "passive"))
      (node (ref "C27") (pin "2") (pinfunction "2_2") (pintype "passive"))
      (node (ref "C28") (pin "2") (pinfunction "2_2") (pintype "passive"))
      (node (ref "C29") (pin "2") (pinfunction "2_2") (pintype "passive"))
      (node (ref "C3") (pin "C") (pinfunction "-_C") (pintype "passive"))
      (node (ref "C30") (pin "2") (pinfunction "2_2") (pintype "passive"))
      (node (ref "C32") (pin "2") (pinfunction "2_2") (pintype "passive"))
      (node (ref "C33") (pin "2") (pinfunction "2_2") (pintype "passive"))
      (node (ref "C34") (pin "2") (pinfunction "2_2") (pintype "passive"))
      (node (ref "C35") (pin "2") (pinfunction "2_2") (pintype "passive"))
      (node (ref "C36") (pin "2") (pinfunction "2_2") (pintype "passive"))
      (node (ref "C37") (pin "2") (pinfunction "2_2") (pintype "passive"))
      (node (ref "C38") (pin "2") (pinfunction "2_2") (pintype "passive"))
      (node (ref "C39") (pin "2") (pinfunction "2_2") (pintype "passive"))
      (node (ref "C4") (pin "C") (pinfunction "-_C") (pintype "passive"))
      (node (ref "C40") (pin "2") (pinfunction "2_2") (pintype "passive"))
      (node (ref "C41") (pin "2") (pinfunction "2_2") (pintype "passive"))
      (node (ref "C42") (pin "2") (pinfunction "2_2") (pintype "passive"))
      (node (ref "C43") (pin "2") (pinfunction "2_2") (pintype "passive"))
      (node (ref "C44") (pin "2") (pinfunction "2_2") (pintype "passive"))
      (node (ref "C45") (pin "2") (pinfunction "2_2") (pintype "passive"))
      (node (ref "C46") (pin "2") (pinfunction "2_2") (pintype "passive"))
      (node (ref "C5") (pin "2") (pinfunction "2_2") (pintype "passive"))
      (node (ref "C6") (pin "2") (pinfunction "2_2") (pintype "passive"))
      (node (ref "C7") (pin "2") (pinfunction "2_2") (pintype "passive"))
      (node (ref "C8") (pin "2") (pinfunction "2_2") (pintype "passive"))
      (node (ref "GND") (pin "PAD") (pinfunction "P_PAD") (pintype "passive"))
      (node (ref "J1") (pin "1") (pinfunction "1_1") (pintype "passive"))
      (node (ref "J2") (pin "11") (pinfunction "MS_11") (pintype "passive"))
      (node (ref "J2") (pin "14") (pinfunction "MS_14") (pintype "passive"))
      (node (ref "J2") (pin "17") (pinfunction "MS_17") (pintype "passive"))
      (node (ref "J2") (pin "20") (pinfunction "MS_20") (pintype "passive"))
      (node (ref "J2") (pin "23") (pinfunction "MS_23") (pintype "passive"))
      (node (ref "J2") (pin "8") (pinfunction "MS_8") (pintype "passive"))
      (node (ref "J3") (pin "1") (pinfunction "1_1") (pintype "passive"))
      (node (ref "R5") (pin "2") (pinfunction "2_2") (pintype "passive"))
      (node (ref "R6") (pin "2") (pinfunction "2_2") (pintype "passive"))
      (node (ref "S1") (pin "1") (pinfunction "1_1") (pintype "passive"))
      (node (ref "S1") (pin "2") (pinfunction "1_2") (pintype "passive"))
      (node (ref "SD1") (pin "6") (pinfunction "VSS_6") (pintype "power_in"))
      (node (ref "SD1") (pin "S1") (pinfunction "S1_S1") (pintype "passive"))
      (node (ref "SD1") (pin "S2") (pinfunction "S2_S2") (pintype "passive"))
      (node (ref "SD1") (pin "S3") (pinfunction "S3_S3") (pintype "passive"))
      (node (ref "SD1") (pin "S4") (pinfunction "S4_S4") (pintype "passive"))
      (node (ref "U0") (pin "108") (pinfunction "GNDA2_108") (pintype "power_in"))
      (node (ref "U0") (pin "118") (pinfunction "GND_118") (pintype "power_in"))
      (node (ref "U0") (pin "123") (pinfunction "GND_123") (pintype "power_in"))
      (node (ref "U0") (pin "131") (pinfunction "GND_131") (pintype "power_in"))
      (node (ref "U0") (pin "140") (pinfunction "GND_140") (pintype "power_in"))
      (node (ref "U0") (pin "145") (pinfunction "EXP_145") (pintype "power_in"))
      (node (ref "U0") (pin "19") (pinfunction "GND_19") (pintype "power_in"))
      (node (ref "U0") (pin "2") (pinfunction "GNDA3_2") (pintype "power_in"))
      (node (ref "U0") (pin "21") (pinfunction "NCE_21") (pintype "bidirectional"))
      (node (ref "U0") (pin "22") (pinfunction "GND_22") (pintype "power_in"))
      (node (ref "U0") (pin "27") (pinfunction "GND_27") (pintype "power_in"))
      (node (ref "U0") (pin "36") (pinfunction "GNDA1_36") (pintype "power_in"))
      (node (ref "U0") (pin "4") (pinfunction "GND_4") (pintype "power_in"))
      (node (ref "U0") (pin "41") (pinfunction "GND_41") (pintype "power_in"))
      (node (ref "U0") (pin "48") (pinfunction "GND_48") (pintype "power_in"))
      (node (ref "U0") (pin "57") (pinfunction "GND_57") (pintype "power_in"))
      (node (ref "U0") (pin "63") (pinfunction "GND_63") (pintype "power_in"))
      (node (ref "U0") (pin "74") (pinfunction "GNDA4_74") (pintype "power_in"))
      (node (ref "U0") (pin "79") (pinfunction "GND_79") (pintype "power_in"))
      (node (ref "U0") (pin "82") (pinfunction "GND_82") (pintype "power_in"))
      (node (ref "U0") (pin "95") (pinfunction "GND_95") (pintype "power_in"))
      (node (ref "U1") (pin "1") (pinfunction "ADJ_1") (pintype "input"))
      (node (ref "U2") (pin "1") (pinfunction "ADJ_1") (pintype "input"))
      (node (ref "U3") (pin "1") (pinfunction "ADJ_1") (pintype "input"))
      (node (ref "U4") (pin "12") (pinfunction "VSSQ_12") (pintype "power_in"))
      (node (ref "U4") (pin "19") (pinfunction "\\CS_19") (pintype "input"))
      (node (ref "U4") (pin "28") (pinfunction "VSS_28") (pintype "power_in"))
      (node (ref "U4") (pin "41") (pinfunction "VSS_41") (pintype "power_in"))
      (node (ref "U4") (pin "46") (pinfunction "VSSQ_46") (pintype "power_in"))
      (node (ref "U4") (pin "52") (pinfunction "VSSQ_52") (pintype "power_in"))
      (node (ref "U4") (pin "54") (pinfunction "VSS_54") (pintype "power_in"))
      (node (ref "U4") (pin "6") (pinfunction "VSSQ_6") (pintype "power_in"))
      (node (ref "U5") (pin "2") (pinfunction "GND_2") (pintype "bidirectional"))
      (node (ref "U6") (pin "4") (pinfunction "GND_4") (pintype "bidirectional"))
      (node (ref "X1") (pin "2") (pinfunction "2_2") (pintype "passive"))
      (node (ref "X1") (pin "2@2") (pinfunction "2_2@2") (pintype "passive"))
    )
    (net (code "73") (name "Net-(D5-PadC)") (class "Default")
      (node (ref "D5") (pin "C") (pinfunction "C_C") (pintype "passive"))
      (node (ref "R5") (pin "1") (pinfunction "1_1") (pintype "passive"))
    )
    (net (code "74") (name "Net-(D6-PadC)") (class "Default")
      (node (ref "D6") (pin "C") (pinfunction "C_C") (pintype "passive"))
      (node (ref "R6") (pin "1") (pinfunction "1_1") (pintype "passive"))
    )
    (net (code "75") (name "Net-(U0-CLK1)") (class "Default")
      (node (ref "U0") (pin "23") (pinfunction "CLK1_23") (pintype "input"))
      (node (ref "U5") (pin "3") (pinfunction "OUT_3") (pintype "bidirectional"))
    )
    (net (code "76") (name "Net-(U0-CLK11)") (class "Default")
      (node (ref "S1") (pin "3") (pinfunction "2_3") (pintype "passive"))
      (node (ref "S1") (pin "4") (pinfunction "2_4") (pintype "passive"))
      (node (ref "U0") (pin "129") (pinfunction "CLK11_129") (pintype "bidirectional"))
    )
    (net (code "77") (name "Net-(U0-NCONFIG)") (class "Default")
      (node (ref "R3") (pin "1") (pinfunction "1_1") (pintype "passive"))
      (node (ref "U0") (pin "14") (pinfunction "NCONFIG_14") (pintype "bidirectional"))
    )
    (net (code "78") (name "Net-(U0-NSTATUS)") (class "Default")
      (node (ref "R4") (pin "1") (pinfunction "1_1") (pintype "passive"))
      (node (ref "U0") (pin "9") (pinfunction "NSTATUS_9") (pintype "bidirectional"))
    )
    (net (code "79") (name "Net-(U0-TCK)") (class "Default")
      (node (ref "J3") (pin "4") (pinfunction "4_4") (pintype "passive"))
      (node (ref "U0") (pin "16") (pinfunction "TCK_16") (pintype "bidirectional"))
    )
    (net (code "80") (name "Net-(U0-TDI)") (class "Default")
      (node (ref "J3") (pin "5") (pinfunction "5_5") (pintype "passive"))
      (node (ref "U0") (pin "15") (pinfunction "TDI_15") (pintype "bidirectional"))
    )
    (net (code "81") (name "Net-(U0-TDO)") (class "Default")
      (node (ref "J3") (pin "2") (pinfunction "2_2") (pintype "passive"))
      (node (ref "U0") (pin "20") (pinfunction "TDO_20") (pintype "bidirectional"))
    )
    (net (code "82") (name "Net-(U0-TMS)") (class "Default")
      (node (ref "J3") (pin "3") (pinfunction "3_3") (pintype "passive"))
      (node (ref "U0") (pin "18") (pinfunction "TMS_18") (pintype "bidirectional"))
    )
    (net (code "83") (name "VCCA") (class "Default")
      (node (ref "C39") (pin "1") (pinfunction "1_1") (pintype "passive"))
      (node (ref "C40") (pin "1") (pinfunction "1_1") (pintype "passive"))
      (node (ref "C41") (pin "1") (pinfunction "1_1") (pintype "passive"))
      (node (ref "C42") (pin "1") (pinfunction "1_1") (pintype "passive"))
      (node (ref "L1") (pin "2") (pinfunction "2_2") (pintype "passive"))
      (node (ref "U0") (pin "107") (pinfunction "VCCA2_107") (pintype "power_in"))
      (node (ref "U0") (pin "3") (pinfunction "VCCA3_3") (pintype "power_in"))
      (node (ref "U0") (pin "35") (pinfunction "VCCA1_35") (pintype "power_in"))
      (node (ref "U0") (pin "75") (pinfunction "VCCA4_75") (pintype "power_in"))
    )
    (net (code "84") (name "VCC_PLL") (class "Default")
      (node (ref "C43") (pin "1") (pinfunction "1_1") (pintype "passive"))
      (node (ref "C44") (pin "1") (pinfunction "1_1") (pintype "passive"))
      (node (ref "C45") (pin "1") (pinfunction "1_1") (pintype "passive"))
      (node (ref "C46") (pin "1") (pinfunction "1_1") (pintype "passive"))
      (node (ref "L2") (pin "2") (pinfunction "2_2") (pintype "passive"))
      (node (ref "U0") (pin "1") (pinfunction "VCCD_PLL3_1") (pintype "power_in"))
      (node (ref "U0") (pin "109") (pinfunction "VCCD_PLL2_109") (pintype "power_in"))
      (node (ref "U0") (pin "37") (pinfunction "VCCD_PLL1_37") (pintype "power_in"))
      (node (ref "U0") (pin "73") (pinfunction "VCCD_PLL4_73") (pintype "power_in"))
    )
    (net (code "85") (name "unconnected-(C1-+-PadA)") (class "Default")
      (node (ref "C1") (pin "A") (pinfunction "+_A") (pintype "passive"))
    )
    (net (code "86") (name "unconnected-(C1---PadC)") (class "Default")
      (node (ref "C1") (pin "C") (pinfunction "-_C") (pintype "passive"))
    )
    (net (code "87") (name "unconnected-(C2-Pad1)") (class "Default")
      (node (ref "C2") (pin "1") (pinfunction "1_1") (pintype "passive"))
    )
    (net (code "88") (name "unconnected-(C2-Pad2)") (class "Default")
      (node (ref "C2") (pin "2") (pinfunction "2_2") (pintype "passive"))
    )
    (net (code "89") (name "unconnected-(D1-PadC)") (class "Default")
      (node (ref "D1") (pin "C") (pinfunction "C_C") (pintype "passive"))
    )
    (net (code "90") (name "unconnected-(D2-PadC)") (class "Default")
      (node (ref "D2") (pin "C") (pinfunction "C_C") (pintype "passive"))
    )
    (net (code "91") (name "unconnected-(J2Q-MS-Pad24)") (class "Default")
      (node (ref "J2") (pin "24") (pinfunction "MS_24") (pintype "passive"))
    )
    (net (code "92") (name "unconnected-(J2R-MS-Pad25)") (class "Default")
      (node (ref "J2") (pin "25") (pinfunction "MS_25") (pintype "passive"))
    )
    (net (code "93") (name "unconnected-(J2S-MS-Pad26)") (class "Default")
      (node (ref "J2") (pin "26") (pinfunction "MS_26") (pintype "passive"))
    )
    (net (code "94") (name "unconnected-(J2Y-MS-Pad4)") (class "Default")
      (node (ref "J2") (pin "4") (pinfunction "MS_4") (pintype "passive"))
    )
    (net (code "95") (name "unconnected-(J2Z-MS-Pad5)") (class "Default")
      (node (ref "J2") (pin "5") (pinfunction "MS_5") (pintype "passive"))
    )
    (net (code "96") (name "unconnected-(R1-Pad1)") (class "Default")
      (node (ref "R1") (pin "1") (pinfunction "1_1") (pintype "passive"))
    )
    (net (code "97") (name "unconnected-(R1-Pad2)") (class "Default")
      (node (ref "R1") (pin "2") (pinfunction "2_2") (pintype "passive"))
    )
    (net (code "98") (name "unconnected-(TP1-1-PadP$1)") (class "Default")
      (node (ref "TP1") (pin "P$1") (pinfunction "1_P$1") (pintype "bidirectional"))
    )
    (net (code "99") (name "unconnected-(U0-CLK2-Pad24)") (class "Default")
      (node (ref "U0") (pin "24") (pinfunction "CLK2_24") (pintype "input"))
    )
    (net (code "100") (name "unconnected-(U0-CLK3-Pad25)") (class "Default")
      (node (ref "U0") (pin "25") (pinfunction "CLK3_25") (pintype "input"))
    )
    (net (code "101") (name "unconnected-(U0-CLK4-Pad91)") (class "Default")
      (node (ref "U0") (pin "91") (pinfunction "CLK4_91") (pintype "input"))
    )
    (net (code "102") (name "unconnected-(U0-CLK5-Pad90)") (class "Default")
      (node (ref "U0") (pin "90") (pinfunction "CLK5_90") (pintype "input"))
    )
    (net (code "103") (name "unconnected-(U0-CLK6-Pad89)") (class "Default")
      (node (ref "U0") (pin "89") (pinfunction "CLK6_89") (pintype "input"))
    )
    (net (code "104") (name "unconnected-(U0-CLK7-Pad88)") (class "Default")
      (node (ref "U0") (pin "88") (pinfunction "CLK7_88") (pintype "input"))
    )
    (net (code "105") (name "unconnected-(U0-CLK8-Pad126)") (class "Default")
      (node (ref "U0") (pin "126") (pinfunction "CLK8_126") (pintype "bidirectional"))
    )
    (net (code "106") (name "unconnected-(U0-CLK9-Pad127)") (class "Default")
      (node (ref "U0") (pin "127") (pinfunction "CLK9_127") (pintype "bidirectional"))
    )
    (net (code "107") (name "unconnected-(U0-CLK10-Pad128)") (class "Default")
      (node (ref "U0") (pin "128") (pinfunction "CLK10_128") (pintype "bidirectional"))
    )
    (net (code "108") (name "unconnected-(U0-CLK12-Pad55)") (class "Default")
      (node (ref "U0") (pin "55") (pinfunction "CLK12_55") (pintype "bidirectional"))
    )
    (net (code "109") (name "unconnected-(U0-CLK13-Pad54)") (class "Default")
      (node (ref "U0") (pin "54") (pinfunction "CLK13_54") (pintype "bidirectional"))
    )
    (net (code "110") (name "unconnected-(U0-CLK14-Pad53)") (class "Default")
      (node (ref "U0") (pin "53") (pinfunction "CLK14_53") (pintype "bidirectional"))
    )
    (net (code "111") (name "unconnected-(U0-CLK15-Pad52)") (class "Default")
      (node (ref "U0") (pin "52") (pinfunction "CLK15_52") (pintype "bidirectional"))
    )
    (net (code "112") (name "unconnected-(U0-CONF_DONE-Pad92)") (class "Default")
      (node (ref "U0") (pin "92") (pinfunction "CONF_DONE_92") (pintype "bidirectional"))
    )
    (net (code "113") (name "unconnected-(U0-IO-Pad32)") (class "Default")
      (node (ref "U0") (pin "32") (pinfunction "IO_32") (pintype "bidirectional"))
    )
    (net (code "114") (name "unconnected-(U0-IO-Pad33)") (class "Default")
      (node (ref "U0") (pin "33") (pinfunction "IO_33") (pintype "bidirectional"))
    )
    (net (code "115") (name "unconnected-(U0-IO-Pad39)") (class "Default")
      (node (ref "U0") (pin "39") (pinfunction "IO_39") (pintype "bidirectional"))
    )
    (net (code "116") (name "unconnected-(U0-IO-Pad42)") (class "Default")
      (node (ref "U0") (pin "42") (pinfunction "IO_42") (pintype "bidirectional"))
    )
    (net (code "117") (name "unconnected-(U0-IO-Pad43)") (class "Default")
      (node (ref "U0") (pin "43") (pinfunction "IO_43") (pintype "bidirectional"))
    )
    (net (code "118") (name "unconnected-(U0-IO-Pad44)") (class "Default")
      (node (ref "U0") (pin "44") (pinfunction "IO_44") (pintype "bidirectional"))
    )
    (net (code "119") (name "unconnected-(U0-IO-Pad46)") (class "Default")
      (node (ref "U0") (pin "46") (pinfunction "IO_46") (pintype "bidirectional"))
    )
    (net (code "120") (name "unconnected-(U0-IO-Pad49)") (class "Default")
      (node (ref "U0") (pin "49") (pinfunction "IO_49") (pintype "bidirectional"))
    )
    (net (code "121") (name "unconnected-(U0-MSEL0-Pad94)") (class "Default")
      (node (ref "U0") (pin "94") (pinfunction "MSEL0_94") (pintype "bidirectional"))
    )
    (net (code "122") (name "unconnected-(U0-MSEL1-Pad96)") (class "Default")
      (node (ref "U0") (pin "96") (pinfunction "MSEL1_96") (pintype "bidirectional"))
    )
    (net (code "123") (name "unconnected-(U0-MSEL2-Pad97)") (class "Default")
      (node (ref "U0") (pin "97") (pinfunction "MSEL2_97") (pintype "bidirectional"))
    )
    (net (code "124") (name "unconnected-(U1-OUT-Pad4)") (class "Default")
      (node (ref "U1") (pin "4") (pinfunction "OUT_4") (pintype "output"))
    )
    (net (code "125") (name "unconnected-(U2-OUT-Pad4)") (class "Default")
      (node (ref "U2") (pin "4") (pinfunction "OUT_4") (pintype "output"))
    )
    (net (code "126") (name "unconnected-(U3-OUT-Pad4)") (class "Default")
      (node (ref "U3") (pin "4") (pinfunction "OUT_4") (pintype "output"))
    )
    (net (code "127") (name "unconnected-(U4A-NC-Pad40)") (class "Default")
      (node (ref "U4") (pin "40") (pinfunction "NC_40") (pintype "no_connect"))
    )
  )
)
